# Power.net
KiCad netlist of a schematic drawn in Altium Designer
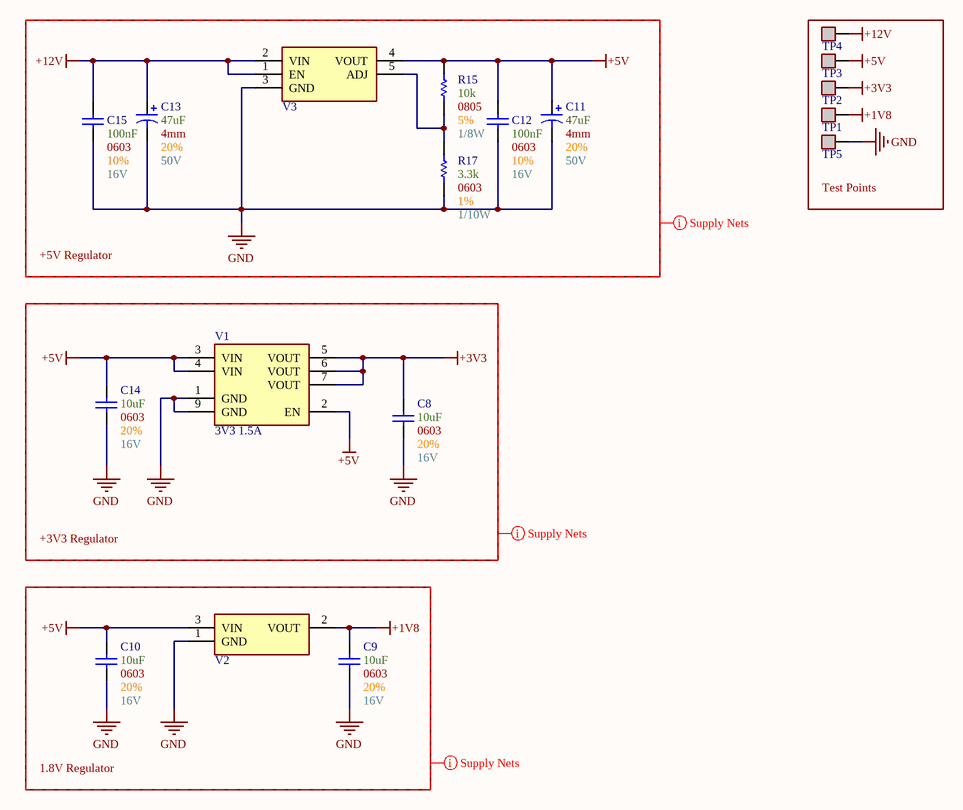
[diagram p0: Power.SchDoc]

(export (version "E")
  (design (tool "Eeschema 10.0.6"))
  (components
    (comp (ref "C8")
      (value "[Cap] 0603 10uF 20% 16V")
      (footprint "[Cap] SMD 0603")
      (description "GRM188C81C106MA73D")
      (fields
        (field (name "MAX VOLTAGE") "16V")
        (field (name "SIZE PACKAGE") "0603")
        (field (name "TOLERANCE") "20%")
        (field (name "CAPACITANCE") "10uF")
      )
      (libsource (lib "Capacitors") (part "[Cap] 0603 10uF 20% 16V"))
    )
    (comp (ref "C9")
      (value "[Cap] 0603 10uF 20% 16V")
      (footprint "[Cap] SMD 0603")
      (description "GRM188C81C106MA73D")
      (fields
        (field (name "MAX VOLTAGE") "16V")
        (field (name "SIZE PACKAGE") "0603")
        (field (name "TOLERANCE") "20%")
        (field (name "CAPACITANCE") "10uF")
      )
      (libsource (lib "Capacitors") (part "[Cap] 0603 10uF 20% 16V"))
    )
    (comp (ref "C10")
      (value "[Cap] 0603 10uF 20% 16V")
      (footprint "[Cap] SMD 0603")
      (description "GRM188C81C106MA73D")
      (fields
        (field (name "MAX VOLTAGE") "16V")
        (field (name "SIZE PACKAGE") "0603")
        (field (name "TOLERANCE") "20%")
        (field (name "CAPACITANCE") "10uF")
      )
      (libsource (lib "Capacitors") (part "[Cap] 0603 10uF 20% 16V"))
    )
    (comp (ref "C11")
      (value "[Cap] 4mm 47uF 20% 50V")
      (footprint "[Cap] SMD Polarized, 4mm")
      (description "EEE-FN1A470UR")
      (fields
        (field (name "MAX VOLTAGE") "50V")
        (field (name "SIZE PACKAGE") "4mm")
        (field (name "TOLERANCE") "20%")
        (field (name "CAPACITANCE") "47uF")
      )
      (libsource (lib "Capacitors") (part "[Cap] 4mm 47uF 20% 50V"))
    )
    (comp (ref "C12")
      (value "[Cap] 0603 0.1uF 10% 16V")
      (footprint "[Cap] SMD 0603")
      (description "CC0603KRX7R7BB104")
      (fields
        (field (name "MAX VOLTAGE") "16V")
        (field (name "SIZE PACKAGE") "0603")
        (field (name "TOLERANCE") "10%")
        (field (name "CAPACITANCE") "100nF")
      )
      (libsource (lib "Capacitors") (part "[Cap] 0603 0.1uF 10% 16V"))
    )
    (comp (ref "C13")
      (value "[Cap] 4mm 47uF 20% 50V")
      (footprint "[Cap] SMD Polarized, 4mm")
      (description "EEE-FN1A470UR")
      (fields
        (field (name "MAX VOLTAGE") "50V")
        (field (name "SIZE PACKAGE") "4mm")
        (field (name "TOLERANCE") "20%")
        (field (name "CAPACITANCE") "47uF")
      )
      (libsource (lib "Capacitors") (part "[Cap] 4mm 47uF 20% 50V"))
    )
    (comp (ref "C14")
      (value "[Cap] 0603 10uF 20% 16V")
      (footprint "[Cap] SMD 0603")
      (description "GRM188C81C106MA73D")
      (fields
        (field (name "MAX VOLTAGE") "16V")
        (field (name "SIZE PACKAGE") "0603")
        (field (name "TOLERANCE") "20%")
        (field (name "CAPACITANCE") "10uF")
      )
      (libsource (lib "Capacitors") (part "[Cap] 0603 10uF 20% 16V"))
    )
    (comp (ref "C15")
      (value "[Cap] 0603 0.1uF 10% 16V")
      (footprint "[Cap] SMD 0603")
      (description "CC0603KRX7R7BB104")
      (fields
        (field (name "MAX VOLTAGE") "16V")
        (field (name "SIZE PACKAGE") "0603")
        (field (name "TOLERANCE") "10%")
        (field (name "CAPACITANCE") "100nF")
      )
      (libsource (lib "Capacitors") (part "[Cap] 0603 0.1uF 10% 16V"))
    )
    (comp (ref "R15")
      (value "[10k] SMD 0603 1% 1/8W")
      (footprint "[Res] SMD 0603")
      (description "RC0805JR-0710KL")
      (fields
        (field (name "WATTAGE") "1/8W")
        (field (name "TOLERANCE") "5%")
        (field (name "RESISTANCE") "10k")
        (field (name "SIZE PACKAGE") "0805")
      )
      (libsource (lib "Resistors") (part "[10k] SMD 0603 1% 1/8W"))
    )
    (comp (ref "R17")
      (value "[3.3k] SMD 0603 1% 1/10W")
      (footprint "[Res] SMD 0603")
      (description "RC0603FR-073K3L")
      (fields
        (field (name "WATTAGE") "1/10W")
        (field (name "TOLERANCE") "1%")
        (field (name "RESISTANCE") "3.3k")
        (field (name "SIZE PACKAGE") "0603")
      )
      (libsource (lib "Resistors") (part "[3.3k] SMD 0603 1% 1/10W"))
    )
    (comp (ref "TP1")
      (value "[THM] Thru-Hole")
      (footprint "[THM] White")
      (description "5012")
      (libsource (lib "Test Points") (part "[THM] Thru-Hole"))
    )
    (comp (ref "TP2")
      (value "[THM] Thru-Hole")
      (footprint "[THM] White")
      (description "5012")
      (libsource (lib "Test Points") (part "[THM] Thru-Hole"))
    )
    (comp (ref "TP3")
      (value "[THM] Thru-Hole")
      (footprint "[THM] White")
      (description "5012")
      (libsource (lib "Test Points") (part "[THM] Thru-Hole"))
    )
    (comp (ref "TP4")
      (value "[THM] Thru-Hole")
      (footprint "[THM] White")
      (description "5012")
      (libsource (lib "Test Points") (part "[THM] Thru-Hole"))
    )
    (comp (ref "TP5")
      (value "[THM] Thru-Hole")
      (footprint "[THM] White")
      (description "5012")
      (libsource (lib "Test Points") (part "[THM] Thru-Hole"))
    )
    (comp (ref "V1")
      (value "3V3 1.5A")
      (footprint "[Linear] 3V3 1.5A")
      (description "AP7362A-33SP-13")
      (libsource (lib "Voltage Regulators") (part "[Linear] 3V3 1.5A"))
    )
    (comp (ref "V2")
      (value "[Linear] 1.8V 1A")
      (footprint "[Linear] 1.8V 1A")
      (description "NCP1117IST18T3G")
      (libsource (lib "Voltage Regulators") (part "[Linear] 1.8V 1A"))
    )
    (comp (ref "V3")
      (value "[Linear] 1.25-25V 3A")
      (footprint "[Linear] 1.25-25V 3A")
      (description "MIC29302WT")
      (libsource (lib "Voltage Regulators") (part "[Linear] 1.25-25V 3A"))
    )
  )
  (nets
    (net (code "1") (name "+1V8") (class "Default")
      (node (ref "C9") (pin "2") (pinfunction "2_2") (pintype "passive"))
      (node (ref "TP1") (pin "1") (pinfunction "1_1") (pintype "passive"))
      (node (ref "V2") (pin "2") (pinfunction "VOUT_2") (pintype "power_in"))
    )
    (net (code "2") (name "+3V3") (class "Default")
      (node (ref "C8") (pin "2") (pinfunction "2_2") (pintype "passive"))
      (node (ref "TP2") (pin "1") (pinfunction "1_1") (pintype "passive"))
      (node (ref "V1") (pin "5") (pinfunction "VOUT_5") (pintype "passive"))
      (node (ref "V1") (pin "6") (pinfunction "VOUT_6") (pintype "passive"))
      (node (ref "V1") (pin "7") (pinfunction "VOUT_7") (pintype "passive"))
    )
    (net (code "3") (name "+5V") (class "Default")
      (node (ref "C10") (pin "2") (pinfunction "2_2") (pintype "passive"))
      (node (ref "C11") (pin "1") (pinfunction "1_1") (pintype "passive"))
      (node (ref "C12") (pin "2") (pinfunction "2_2") (pintype "passive"))
      (node (ref "C14") (pin "2") (pinfunction "2_2") (pintype "passive"))
      (node (ref "R15") (pin "2") (pinfunction "2_2") (pintype "passive"))
      (node (ref "TP3") (pin "1") (pinfunction "1_1") (pintype "passive"))
      (node (ref "V1") (pin "2") (pinfunction "EN_2") (pintype "passive"))
      (node (ref "V1") (pin "3") (pinfunction "VIN_3") (pintype "passive"))
      (node (ref "V1") (pin "4") (pinfunction "VIN_4") (pintype "passive"))
      (node (ref "V2") (pin "3") (pinfunction "VIN_3") (pintype "power_in"))
      (node (ref "V3") (pin "4") (pinfunction "VOUT_4") (pintype "power_in"))
    )
    (net (code "4") (name "+12V") (class "Default")
      (node (ref "C13") (pin "1") (pinfunction "1_1") (pintype "passive"))
      (node (ref "C15") (pin "2") (pinfunction "2_2") (pintype "passive"))
      (node (ref "TP4") (pin "1") (pinfunction "1_1") (pintype "passive"))
      (node (ref "V3") (pin "1") (pinfunction "EN_1") (pintype "power_in"))
      (node (ref "V3") (pin "2") (pinfunction "VIN_2") (pintype "power_in"))
    )
    (net (code "5") (name "GND") (class "Default")
      (node (ref "C10") (pin "1") (pinfunction "1_1") (pintype "passive"))
      (node (ref "C11") (pin "2") (pinfunction "2_2") (pintype "passive"))
      (node (ref "C12") (pin "1") (pinfunction "1_1") (pintype "passive"))
      (node (ref "C13") (pin "2") (pinfunction "2_2") (pintype "passive"))
      (node (ref "C14") (pin "1") (pinfunction "1_1") (pintype "passive"))
      (node (ref "C15") (pin "1") (pinfunction "1_1") (pintype "passive"))
      (node (ref "C8") (pin "1") (pinfunction "1_1") (pintype "passive"))
      (node (ref "C9") (pin "1") (pinfunction "1_1") (pintype "passive"))
      (node (ref "R17") (pin "1") (pinfunction "1_1") (pintype "passive"))
      (node (ref "TP5") (pin "1") (pinfunction "1_1") (pintype "passive"))
      (node (ref "V1") (pin "1") (pinfunction "GND_1") (pintype "passive"))
      (node (ref "V1") (pin "9") (pinfunction "GND_9") (pintype "passive"))
      (node (ref "V2") (pin "1") (pinfunction "GND_1") (pintype "power_in"))
      (node (ref "V3") (pin "3") (pinfunction "GND_3") (pintype "power_in"))
    )
    (net (code "6") (name "Net-(V3-ADJ)") (class "Default")
      (node (ref "R15") (pin "1") (pinfunction "1_1") (pintype "passive"))
      (node (ref "R17") (pin "2") (pinfunction "2_2") (pintype "passive"))
      (node (ref "V3") (pin "5") (pinfunction "ADJ_5") (pintype "power_in"))
    )
  )
)
